# pc_healthypi_move_nRF5340_v1.net
KiCad netlist of a schematic drawn in EAGLE
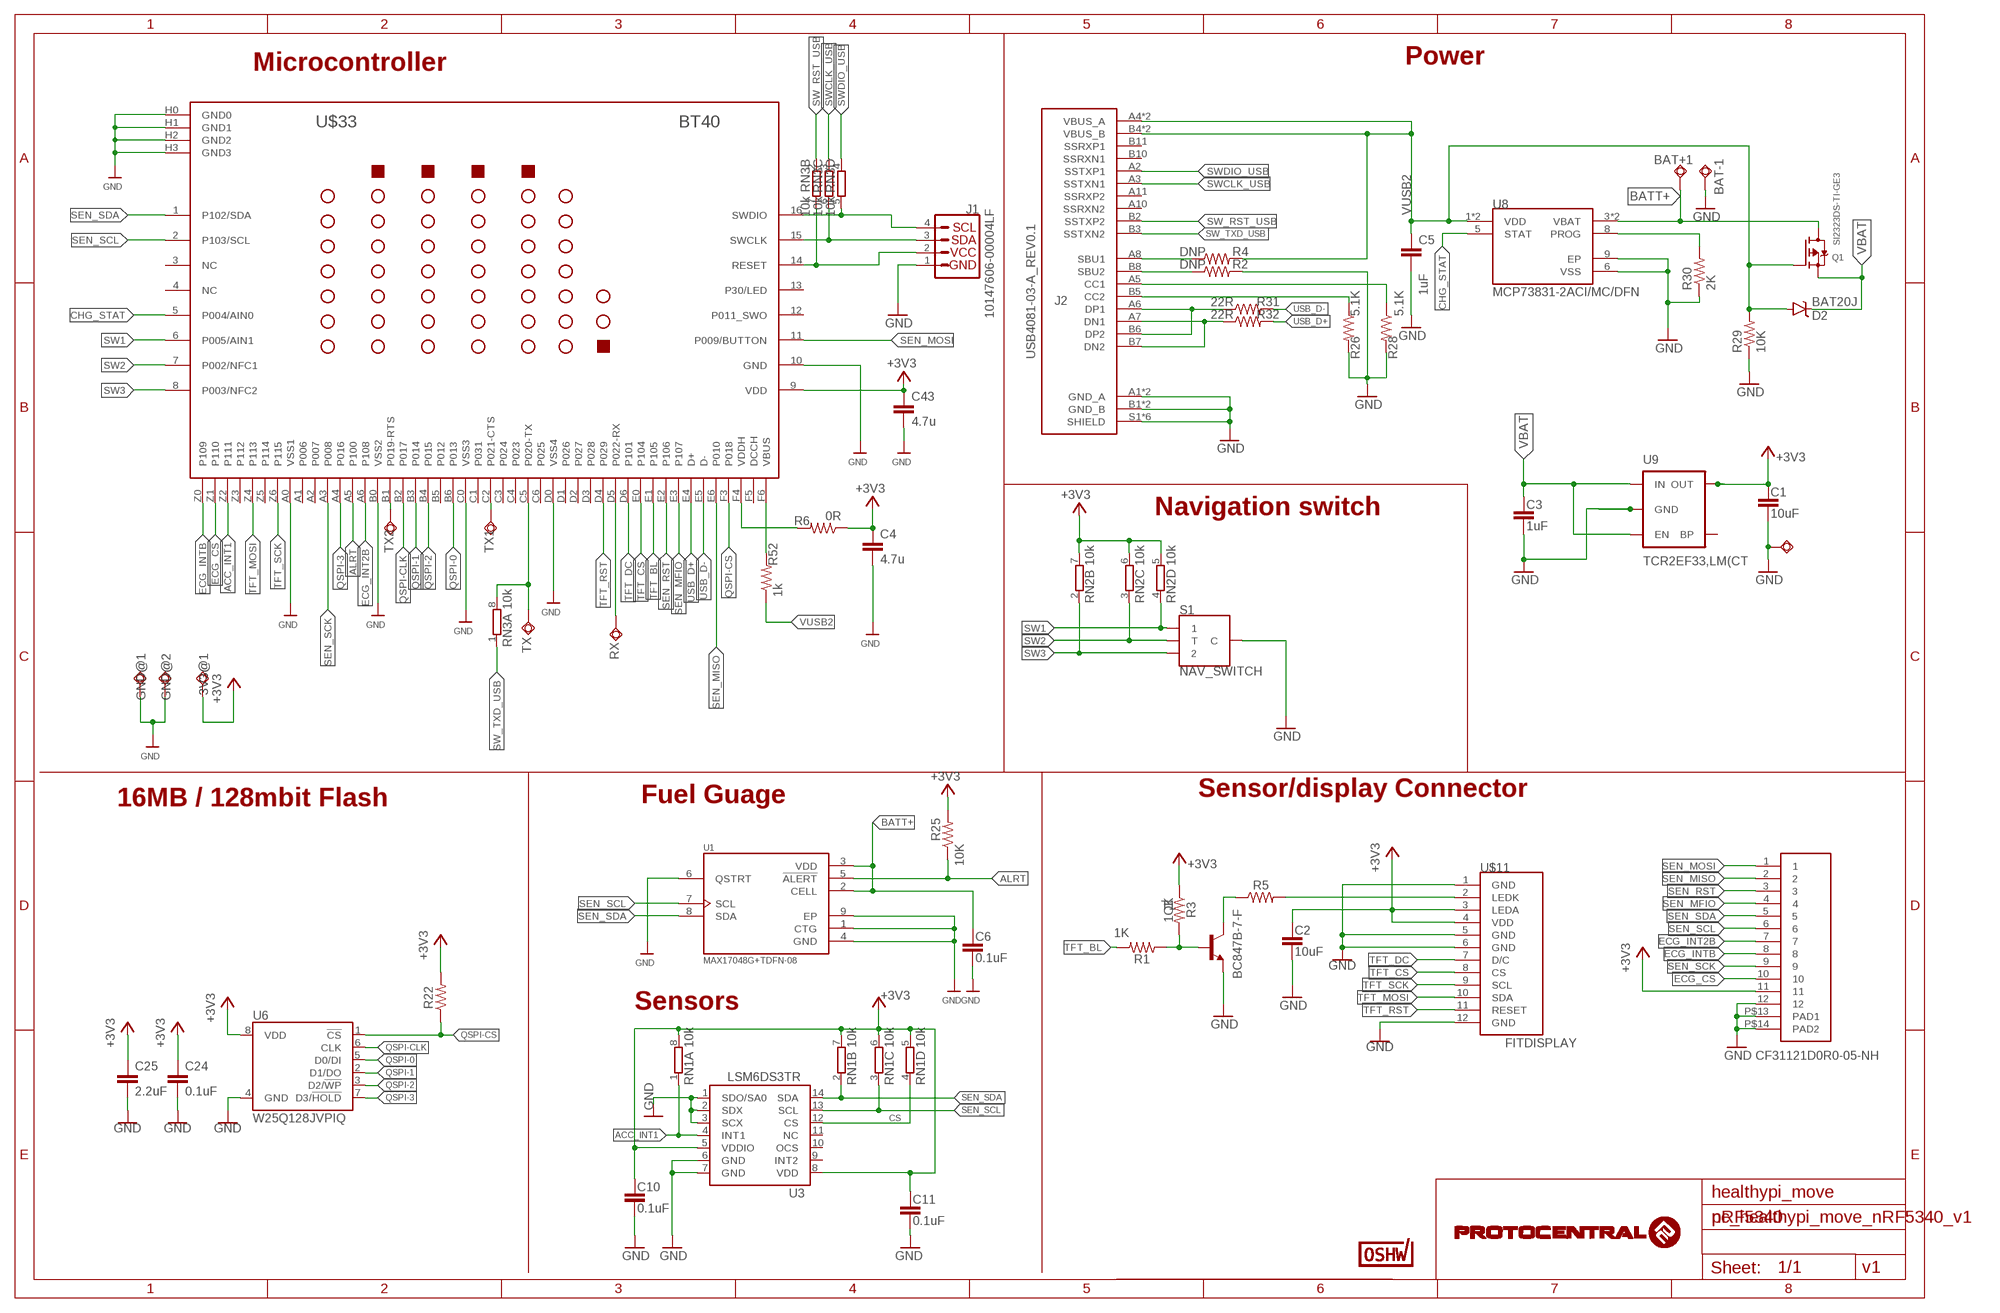
[diagram p0: schematic, sheet 1]

(export (version "E")
  (design (tool "Eeschema 10.0.6"))
  (components
    (comp (ref "3V3@1")
      (value "TPSQTP13SQ")
      (footprint "eagle-import:TP13SQ")
      (libsource (lib "eagle-import") (part "TPSQTP13SQ"))
    )
    (comp (ref "BAT+1")
      (value "TPSQTP13SQ")
      (footprint "eagle-import:TP13SQ")
      (libsource (lib "eagle-import") (part "TPSQTP13SQ"))
    )
    (comp (ref "BAT-1")
      (value "TPSQTP13SQ")
      (footprint "eagle-import:TP13SQ")
      (libsource (lib "eagle-import") (part "TPSQTP13SQ"))
    )
    (comp (ref "C1")
      (value "10uF")
      (footprint "eagle-import:0603@1")
      (libsource (lib "eagle-import") (part "0.1UF-0603-100V-10%"))
    )
    (comp (ref "C2")
      (value "10uF")
      (footprint "eagle-import:0603@1")
      (libsource (lib "eagle-import") (part "0.1UF-0603-100V-10%"))
    )
    (comp (ref "C3")
      (value "1uF")
      (footprint "eagle-import:0402-TIGHT")
      (libsource (lib "eagle-import") (part "0.1UF-0402T-6.3V-10%-X7R"))
    )
    (comp (ref "C4")
      (value "4.7u")
      (footprint "eagle-import:C0402")
      (libsource (lib "eagle-import") (part "C-EUC0402"))
    )
    (comp (ref "C5")
      (value "1uF")
      (footprint "eagle-import:0402-TIGHT")
      (libsource (lib "eagle-import") (part "2.2UF-0402_TIGHT-10V-10%-X5R"))
    )
    (comp (ref "C6")
      (value "0.1uF")
      (footprint "eagle-import:0402-TIGHT")
      (libsource (lib "eagle-import") (part "0.1UF-0402T-6.3V-10%-X7R"))
    )
    (comp (ref "C10")
      (value "0.1uF")
      (footprint "eagle-import:0402-TIGHT")
      (libsource (lib "eagle-import") (part "0.1UF-0402T-6.3V-10%-X7R"))
    )
    (comp (ref "C11")
      (value "0.1uF")
      (footprint "eagle-import:0402-TIGHT")
      (libsource (lib "eagle-import") (part "0.1UF-0402T-6.3V-10%-X7R"))
    )
    (comp (ref "C24")
      (value "0.1uF")
      (footprint "eagle-import:0402-TIGHT")
      (libsource (lib "eagle-import") (part "0.1UF-0402T-6.3V-10%-X7R"))
    )
    (comp (ref "C25")
      (value "2.2uF")
      (footprint "eagle-import:0402-TIGHT")
      (libsource (lib "eagle-import") (part "2.2UF-0402_TIGHT-10V-10%-X5R"))
    )
    (comp (ref "C43")
      (value "4.7u")
      (footprint "eagle-import:C0402")
      (libsource (lib "eagle-import") (part "C-EUC0402"))
    )
    (comp (ref "D2")
      (value "BAT20J")
      (footprint "eagle-import:SOD-323")
      (libsource (lib "eagle-import") (part "DIODE-SCHOTTKY-BAT20J"))
    )
    (comp (ref "GND@1")
      (value "TPSQTP13SQ")
      (footprint "eagle-import:TP13SQ")
      (libsource (lib "eagle-import") (part "TPSQTP13SQ"))
    )
    (comp (ref "GND@2")
      (value "TPSQTP13SQ")
      (footprint "eagle-import:TP13SQ")
      (libsource (lib "eagle-import") (part "TPSQTP13SQ"))
    )
    (comp (ref "J1")
      (value "10147606-00004LF")
      (footprint "eagle-import:JST04_1MM_RA")
      (libsource (lib "eagle-import") (part "QWIIC_CONNECTORJS-1MM"))
    )
    (comp (ref "J2")
      (value "USB4081-03-A_REV0.1")
      (footprint "eagle-import:GCT_USB4081-03-A_REV0.1")
      (fields (field (name "MF") "Global Connector Technology") (field (name "MP") "USB4081-03-A"))
      (libsource (lib "eagle-import") (part "USB4081-03-A_REV0.1"))
    )
    (comp (ref "Q1")
      (value "SI2323DS-TI-GE3")
      (footprint "eagle-import:SOT23-R")
      (libsource (lib "eagle-import") (part "MOSFET-P"))
    )
    (comp (ref "R1")
      (value "200")
      (footprint "eagle-import:R0402")
      (libsource (lib "eagle-import") (part "R-US_R0402"))
    )
    (comp (ref "R2")
      (value "DNP")
      (footprint "eagle-import:0402-RES")
      (libsource (lib "eagle-import") (part "RESISTOR0402-RES"))
    )
    (comp (ref "R3")
      (value "200")
      (footprint "eagle-import:R0402")
      (libsource (lib "eagle-import") (part "R-US_R0402"))
    )
    (comp (ref "R4")
      (value "DNP")
      (footprint "eagle-import:0402-RES")
      (libsource (lib "eagle-import") (part "RESISTOR0402-RES"))
    )
    (comp (ref "R5")
      (value "200R")
      (footprint "eagle-import:R0402")
      (libsource (lib "eagle-import") (part "R-US_R0402"))
    )
    (comp (ref "R6")
      (value "0R")
      (footprint "eagle-import:0402-RES")
      (libsource (lib "eagle-import") (part "RESISTOR0402-RES"))
    )
    (comp (ref "R22")
      (value "10k")
      (footprint "eagle-import:R0402")
      (libsource (lib "eagle-import") (part "R-US_R0402"))
    )
    (comp (ref "R25")
      (value "10K")
      (footprint "eagle-import:0402-RES")
      (libsource (lib "eagle-import") (part "RESISTOR0402-RES"))
    )
    (comp (ref "R26")
      (value "5.1K")
      (footprint "eagle-import:0402-RES")
      (libsource (lib "eagle-import") (part "RESISTOR0402-RES"))
    )
    (comp (ref "R28")
      (value "5.1K")
      (footprint "eagle-import:0402-RES")
      (libsource (lib "eagle-import") (part "RESISTOR0402-RES"))
    )
    (comp (ref "R29")
      (value "10K")
      (footprint "eagle-import:R0402")
      (libsource (lib "eagle-import") (part "R-US_R0402"))
    )
    (comp (ref "R30")
      (value "2K")
      (footprint "eagle-import:R0402")
      (libsource (lib "eagle-import") (part "R-US_R0402"))
    )
    (comp (ref "R31")
      (value "22R")
      (footprint "eagle-import:0402-RES")
      (libsource (lib "eagle-import") (part "RESISTOR0402-RES"))
    )
    (comp (ref "R32")
      (value "22R")
      (footprint "eagle-import:0402-RES")
      (libsource (lib "eagle-import") (part "RESISTOR0402-RES"))
    )
    (comp (ref "R52")
      (value "1k")
      (footprint "eagle-import:0402-RES")
      (libsource (lib "eagle-import") (part "RESISTOR0402-RES"))
    )
    (comp (ref "RN1")
      (value "10k")
      (footprint "eagle-import:4X0402ARV341")
      (libsource (lib "eagle-import") (part "4R-N0402ARV341"))
    )
    (comp (ref "RN2")
      (value "10k")
      (footprint "eagle-import:4X0402ARV341")
      (libsource (lib "eagle-import") (part "4R-N0402ARV341"))
    )
    (comp (ref "RN3")
      (value "10k")
      (footprint "eagle-import:4X0402ARV341")
      (libsource (lib "eagle-import") (part "4R-N0402ARV341"))
    )
    (comp (ref "RX")
      (value "TPSQTP13SQ")
      (footprint "eagle-import:TP13SQ")
      (libsource (lib "eagle-import") (part "TPSQTP13SQ"))
    )
    (comp (ref "S1")
      (value "NAV_SWITCH")
      (footprint "eagle-import:NAV_SWITCH")
      (libsource (lib "eagle-import") (part "NAV_SWITCH"))
    )
    (comp (ref "SWIO6")
      (value "TPSQTP11R")
      (footprint "eagle-import:TP11R")
      (libsource (lib "eagle-import") (part "TPSQTP11R"))
    )
    (comp (ref "T1")
      (value "BC847B-7-F")
      (footprint "eagle-import:SOT23-BEC")
      (libsource (lib "eagle-import") (part "-NPN-SOT23-BECMMBT2222ALT1"))
    )
    (comp (ref "TX")
      (value "TPSQTP13SQ")
      (footprint "eagle-import:TP13SQ")
      (libsource (lib "eagle-import") (part "TPSQTP13SQ"))
    )
    (comp (ref "TX1")
      (value "TPSQTP13SQ")
      (footprint "eagle-import:TP13SQ")
      (libsource (lib "eagle-import") (part "TPSQTP13SQ"))
    )
    (comp (ref "TX2")
      (value "TPSQTP13SQ")
      (footprint "eagle-import:TP13SQ")
      (libsource (lib "eagle-import") (part "TPSQTP13SQ"))
    )
    (comp (ref "U$5")
      (value "CF31121D0R0-05-NH")
      (footprint "eagle-import:CF31121D0R0-05-NH")
      (libsource (lib "eagle-import") (part "CF31121D0R0-05-NH"))
    )
    (comp (ref "U$9")
      (value "CERT-SMALL")
      (footprint "eagle-import:CERT-SMALL-SILK")
      (libsource (lib "eagle-import") (part "CERT-SMALL"))
    )
    (comp (ref "U$11")
      (value "FITDISPLAY")
      (footprint "eagle-import:FITDISPLAY")
      (libsource (lib "eagle-import") (part "FITDISPLAY"))
    )
    (comp (ref "U$33")
      (value "BT40")
      (footprint "eagle-import:BT40")
      (libsource (lib "eagle-import") (part "BT40"))
    )
    (comp (ref "U1")
      (value "MAX17048G+TDFN-08")
      (footprint "eagle-import:SON50P200X200X80-9N")
      (fields (field (name "MF") "Analog Devices") (field (name "MP") "MAX17048G+"))
      (libsource (lib "eagle-import") (part "MAX17048G+TDFN-08"))
    )
    (comp (ref "U3")
      (value "LSM6DS3TR")
      (footprint "eagle-import:LGA14L")
      (libsource (lib "eagle-import") (part "LSM6DS3"))
    )
    (comp (ref "U6")
      (value "W25Q128JVPIQ")
      (footprint "eagle-import:WSON-8-6X5-SKINNY_CENTERPAD")
      (libsource (lib "eagle-import") (part "W25QXX128MBIT-6X5-SKINNY_CENTER"))
    )
    (comp (ref "U8")
      (value "MCP73831-2ACI/MC/DFN")
      (footprint "eagle-import:SON50P200X300X100-9N")
      (fields (field (name "MF") "Microchip Technology") (field (name "MP") "MCP73831-2ACI/MC"))
      (libsource (lib "eagle-import") (part "MCP73831-2ACI/MC/DFN"))
    )
    (comp (ref "U9")
      (value "TCR2EF33,LM(CT")
      (footprint "eagle-import:SOT23-5")
      (libsource (lib "eagle-import") (part "V_REG_LDOSMD"))
    )
  )
  (nets
    (net (code "1") (name "+3V3") (class "Default")
      (node (ref "3V3@1") (pin "TP") (pinfunction "TP_TP") (pintype "input"))
      (node (ref "C1") (pin "1") (pinfunction "1_1") (pintype "passive"))
      (node (ref "C10") (pin "1") (pinfunction "1_1") (pintype "passive"))
      (node (ref "C11") (pin "1") (pinfunction "1_1") (pintype "passive"))
      (node (ref "C2") (pin "1") (pinfunction "1_1") (pintype "passive"))
      (node (ref "C24") (pin "1") (pinfunction "1_1") (pintype "passive"))
      (node (ref "C25") (pin "1") (pinfunction "1_1") (pintype "passive"))
      (node (ref "C4") (pin "1") (pinfunction "1_1") (pintype "passive"))
      (node (ref "C43") (pin "1") (pinfunction "1_1") (pintype "passive"))
      (node (ref "R22") (pin "2") (pinfunction "2_2") (pintype "passive"))
      (node (ref "R25") (pin "2") (pinfunction "2_2") (pintype "passive"))
      (node (ref "R3") (pin "1") (pinfunction "1_1") (pintype "passive"))
      (node (ref "R6") (pin "1") (pinfunction "1_1") (pintype "passive"))
      (node (ref "RN1") (pin "5") (pinfunction "2_5") (pintype "passive"))
      (node (ref "RN1") (pin "6") (pinfunction "2_6") (pintype "passive"))
      (node (ref "RN1") (pin "7") (pinfunction "2_7") (pintype "passive"))
      (node (ref "RN1") (pin "8") (pinfunction "2_8") (pintype "passive"))
      (node (ref "RN2") (pin "5") (pinfunction "2_5") (pintype "passive"))
      (node (ref "RN2") (pin "6") (pinfunction "2_6") (pintype "passive"))
      (node (ref "RN2") (pin "7") (pinfunction "2_7") (pintype "passive"))
      (node (ref "U$11") (pin "3") (pinfunction "LEDA_3") (pintype "bidirectional"))
      (node (ref "U$11") (pin "4") (pinfunction "VDD_4") (pintype "bidirectional"))
      (node (ref "U$33") (pin "9") (pinfunction "VDD_9") (pintype "bidirectional"))
      (node (ref "U$5") (pin "11") (pinfunction "11_11") (pintype "bidirectional"))
      (node (ref "U3") (pin "5") (pinfunction "VDDIO_5") (pintype "bidirectional"))
      (node (ref "U3") (pin "8") (pinfunction "VDD_8") (pintype "bidirectional"))
      (node (ref "U6") (pin "8") (pinfunction "VDD_8") (pintype "bidirectional"))
      (node (ref "U9") (pin "5") (pinfunction "OUT_5") (pintype "passive"))
    )
    (net (code "2") (name "/CS") (class "Default")
      (node (ref "RN1") (pin "4") (pinfunction "1_4") (pintype "passive"))
      (node (ref "U3") (pin "12") (pinfunction "CS_12") (pintype "bidirectional"))
    )
    (net (code "3") (name "ACC_INT1") (class "Default")
      (node (ref "RN1") (pin "1") (pinfunction "1_1") (pintype "passive"))
      (node (ref "U$33") (pin "Z2") (pinfunction "P111_Z2") (pintype "bidirectional"))
      (node (ref "U3") (pin "4") (pinfunction "INT1_4") (pintype "bidirectional"))
    )
    (net (code "4") (name "ALRT") (class "Default")
      (node (ref "R25") (pin "1") (pinfunction "1_1") (pintype "passive"))
      (node (ref "U$33") (pin "A5") (pinfunction "P100_A5") (pintype "bidirectional"))
      (node (ref "U1") (pin "5") (pinfunction "~{ALERT}_5") (pintype "output"))
    )
    (net (code "5") (name "BATT+") (class "Default")
      (node (ref "BAT+1") (pin "TP") (pinfunction "TP_TP") (pintype "input"))
      (node (ref "C6") (pin "1") (pinfunction "1_1") (pintype "passive"))
      (node (ref "Q1") (pin "3") (pinfunction "D_3") (pintype "passive"))
      (node (ref "U1") (pin "2") (pinfunction "CELL_2") (pintype "power_in"))
      (node (ref "U1") (pin "3") (pinfunction "VDD_3") (pintype "power_in"))
      (node (ref "U8") (pin "3") (pinfunction "VBAT_3") (pintype "output"))
      (node (ref "U8") (pin "4") (pinfunction "VBAT_4") (pintype "output"))
    )
    (net (code "6") (name "CHG_STAT") (class "Default")
      (node (ref "U$33") (pin "5") (pinfunction "P004/AIN0_5") (pintype "bidirectional"))
      (node (ref "U8") (pin "5") (pinfunction "STAT_5") (pintype "output"))
    )
    (net (code "7") (name "ECG_CS") (class "Default")
      (node (ref "U$33") (pin "Z1") (pinfunction "P110_Z1") (pintype "bidirectional"))
      (node (ref "U$5") (pin "10") (pinfunction "10_10") (pintype "bidirectional"))
    )
    (net (code "8") (name "ECG_INT2B") (class "Default")
      (node (ref "U$33") (pin "A6") (pinfunction "P108_A6") (pintype "bidirectional"))
      (node (ref "U$5") (pin "7") (pinfunction "7_7") (pintype "bidirectional"))
    )
    (net (code "9") (name "ECG_INTB") (class "Default")
      (node (ref "U$33") (pin "Z0") (pinfunction "P109_Z0") (pintype "bidirectional"))
      (node (ref "U$5") (pin "8") (pinfunction "8_8") (pintype "bidirectional"))
    )
    (net (code "10") (name "GND") (class "Default")
      (node (ref "BAT-1") (pin "TP") (pinfunction "TP_TP") (pintype "input"))
      (node (ref "C1") (pin "2") (pinfunction "2_2") (pintype "passive"))
      (node (ref "C10") (pin "2") (pinfunction "2_2") (pintype "passive"))
      (node (ref "C11") (pin "2") (pinfunction "2_2") (pintype "passive"))
      (node (ref "C2") (pin "2") (pinfunction "2_2") (pintype "passive"))
      (node (ref "C24") (pin "2") (pinfunction "2_2") (pintype "passive"))
      (node (ref "C25") (pin "2") (pinfunction "2_2") (pintype "passive"))
      (node (ref "C3") (pin "2") (pinfunction "2_2") (pintype "passive"))
      (node (ref "C4") (pin "2") (pinfunction "2_2") (pintype "passive"))
      (node (ref "C43") (pin "2") (pinfunction "2_2") (pintype "passive"))
      (node (ref "C5") (pin "2") (pinfunction "2_2") (pintype "passive"))
      (node (ref "C6") (pin "2") (pinfunction "2_2") (pintype "passive"))
      (node (ref "GND@1") (pin "TP") (pinfunction "TP_TP") (pintype "input"))
      (node (ref "GND@2") (pin "TP") (pinfunction "TP_TP") (pintype "input"))
      (node (ref "J1") (pin "1") (pinfunction "1_1") (pintype "power_in"))
      (node (ref "J2") (pin "A1") (pinfunction "GND_A_A1") (pintype "power_in"))
      (node (ref "J2") (pin "A12") (pinfunction "GND_A_A12") (pintype "power_in"))
      (node (ref "J2") (pin "B1") (pinfunction "GND_B_B1") (pintype "power_in"))
      (node (ref "J2") (pin "B12") (pinfunction "GND_B_B12") (pintype "power_in"))
      (node (ref "J2") (pin "S1") (pinfunction "SHIELD_S1") (pintype "passive"))
      (node (ref "J2") (pin "S2") (pinfunction "SHIELD_S2") (pintype "passive"))
      (node (ref "J2") (pin "S3") (pinfunction "SHIELD_S3") (pintype "passive"))
      (node (ref "J2") (pin "S4") (pinfunction "SHIELD_S4") (pintype "passive"))
      (node (ref "J2") (pin "S5") (pinfunction "SHIELD_S5") (pintype "passive"))
      (node (ref "J2") (pin "S6") (pinfunction "SHIELD_S6") (pintype "passive"))
      (node (ref "R2") (pin "2") (pinfunction "2_2") (pintype "passive"))
      (node (ref "R26") (pin "2") (pinfunction "2_2") (pintype "passive"))
      (node (ref "R28") (pin "2") (pinfunction "2_2") (pintype "passive"))
      (node (ref "R29") (pin "1") (pinfunction "1_1") (pintype "passive"))
      (node (ref "R30") (pin "1") (pinfunction "1_1") (pintype "passive"))
      (node (ref "S1") (pin "C") (pinfunction "C_C") (pintype "power_in"))
      (node (ref "SWIO6") (pin "TP") (pinfunction "TP_TP") (pintype "input"))
      (node (ref "T1") (pin "E") (pinfunction "E_E") (pintype "passive"))
      (node (ref "U$11") (pin "1") (pinfunction "GND_1") (pintype "bidirectional"))
      (node (ref "U$11") (pin "12") (pinfunction "GND_12") (pintype "bidirectional"))
      (node (ref "U$11") (pin "5") (pinfunction "GND_5") (pintype "bidirectional"))
      (node (ref "U$11") (pin "6") (pinfunction "GND_6") (pintype "bidirectional"))
      (node (ref "U$33") (pin "10") (pinfunction "GND_10") (pintype "bidirectional"))
      (node (ref "U$33") (pin "A0") (pinfunction "VSS1_A0") (pintype "bidirectional"))
      (node (ref "U$33") (pin "B0") (pinfunction "VSS2_B0") (pintype "bidirectional"))
      (node (ref "U$33") (pin "C0") (pinfunction "VSS3_C0") (pintype "bidirectional"))
      (node (ref "U$33") (pin "D0") (pinfunction "VSS4_D0") (pintype "bidirectional"))
      (node (ref "U$33") (pin "H0") (pinfunction "GND0_H0") (pintype "bidirectional"))
      (node (ref "U$33") (pin "H1") (pinfunction "GND1_H1") (pintype "bidirectional"))
      (node (ref "U$33") (pin "H2") (pinfunction "GND2_H2") (pintype "bidirectional"))
      (node (ref "U$33") (pin "H3") (pinfunction "GND3_H3") (pintype "bidirectional"))
      (node (ref "U$5") (pin "12") (pinfunction "12_12") (pintype "bidirectional"))
      (node (ref "U$5") (pin "P$13") (pinfunction "PAD1_P$13") (pintype "bidirectional"))
      (node (ref "U$5") (pin "P$14") (pinfunction "PAD2_P$14") (pintype "bidirectional"))
      (node (ref "U1") (pin "1") (pinfunction "CTG_1") (pintype "power_in"))
      (node (ref "U1") (pin "4") (pinfunction "GND_4") (pintype "power_in"))
      (node (ref "U1") (pin "6") (pinfunction "QSTRT_6") (pintype "input"))
      (node (ref "U1") (pin "9") (pinfunction "EP_9") (pintype "power_in"))
      (node (ref "U3") (pin "1") (pinfunction "SDO/SA0_1") (pintype "bidirectional"))
      (node (ref "U3") (pin "2") (pinfunction "SDX_2") (pintype "bidirectional"))
      (node (ref "U3") (pin "3") (pinfunction "SCX_3") (pintype "bidirectional"))
      (node (ref "U3") (pin "6") (pinfunction "GND_6") (pintype "bidirectional"))
      (node (ref "U3") (pin "7") (pinfunction "GND_7") (pintype "bidirectional"))
      (node (ref "U6") (pin "4") (pinfunction "GND_4") (pintype "bidirectional"))
      (node (ref "U8") (pin "6") (pinfunction "VSS_6") (pintype "power_in"))
      (node (ref "U8") (pin "9") (pinfunction "EP_9") (pintype "power_in"))
      (node (ref "U9") (pin "2") (pinfunction "GND_2") (pintype "input"))
    )
    (net (code "11") (name "Net-(J2-CC1)") (class "Default")
      (node (ref "J2") (pin "A5") (pinfunction "CC1_A5") (pintype "bidirectional"))
      (node (ref "R28") (pin "1") (pinfunction "1_1") (pintype "passive"))
    )
    (net (code "12") (name "Net-(J2-CC2)") (class "Default")
      (node (ref "J2") (pin "B5") (pinfunction "CC2_B5") (pintype "bidirectional"))
      (node (ref "R26") (pin "1") (pinfunction "1_1") (pintype "passive"))
    )
    (net (code "13") (name "Net-(J2-DN1)") (class "Default")
      (node (ref "J2") (pin "A7") (pinfunction "DN1_A7") (pintype "bidirectional"))
      (node (ref "J2") (pin "B7") (pinfunction "DN2_B7") (pintype "bidirectional"))
      (node (ref "R32") (pin "1") (pinfunction "1_1") (pintype "passive"))
    )
    (net (code "14") (name "Net-(J2-DP1)") (class "Default")
      (node (ref "J2") (pin "A6") (pinfunction "DP1_A6") (pintype "bidirectional"))
      (node (ref "J2") (pin "B6") (pinfunction "DP2_B6") (pintype "bidirectional"))
      (node (ref "R31") (pin "1") (pinfunction "1_1") (pintype "passive"))
    )
    (net (code "15") (name "Net-(J2-SBU1)") (class "Default")
      (node (ref "J2") (pin "A8") (pinfunction "SBU1_A8") (pintype "bidirectional"))
      (node (ref "R4") (pin "1") (pinfunction "1_1") (pintype "passive"))
    )
    (net (code "16") (name "Net-(J2-SBU2)") (class "Default")
      (node (ref "J2") (pin "B8") (pinfunction "SBU2_B8") (pintype "bidirectional"))
      (node (ref "R2") (pin "1") (pinfunction "1_1") (pintype "passive"))
    )
    (net (code "17") (name "Net-(R1-Pad1)") (class "Default")
      (node (ref "R1") (pin "1") (pinfunction "1_1") (pintype "passive"))
      (node (ref "R3") (pin "2") (pinfunction "2_2") (pintype "passive"))
      (node (ref "T1") (pin "B") (pinfunction "B_B") (pintype "passive"))
    )
    (net (code "18") (name "Net-(R5-Pad1)") (class "Default")
      (node (ref "R5") (pin "1") (pinfunction "1_1") (pintype "passive"))
      (node (ref "T1") (pin "C") (pinfunction "C_C") (pintype "passive"))
    )
    (net (code "19") (name "Net-(RN3A-2)") (class "Default")
      (node (ref "RN3") (pin "8") (pinfunction "2_8") (pintype "passive"))
      (node (ref "TX") (pin "TP") (pinfunction "TP_TP") (pintype "input"))
      (node (ref "U$33") (pin "C5") (pinfunction "P020-TX_C5") (pintype "bidirectional"))
    )
    (net (code "20") (name "Net-(RN3B-2)") (class "Default")
      (node (ref "J1") (pin "2") (pinfunction "2_2") (pintype "power_in"))
      (node (ref "RN3") (pin "7") (pinfunction "2_7") (pintype "passive"))
      (node (ref "U$33") (pin "14") (pinfunction "RESET_14") (pintype "bidirectional"))
    )
    (net (code "21") (name "Net-(RN3C-2)") (class "Default")
      (node (ref "J1") (pin "3") (pinfunction "3_3") (pintype "passive"))
      (node (ref "RN3") (pin "6") (pinfunction "2_6") (pintype "passive"))
      (node (ref "U$33") (pin "15") (pinfunction "SWCLK_15") (pintype "bidirectional"))
    )
    (net (code "22") (name "Net-(RN3D-2)") (class "Default")
      (node (ref "J1") (pin "4") (pinfunction "4_4") (pintype "passive"))
      (node (ref "RN3") (pin "5") (pinfunction "2_5") (pintype "passive"))
      (node (ref "U$33") (pin "16") (pinfunction "SWDIO_16") (pintype "bidirectional"))
    )
    (net (code "23") (name "Net-(U$11-LEDK)") (class "Default")
      (node (ref "R5") (pin "2") (pinfunction "2_2") (pintype "passive"))
      (node (ref "U$11") (pin "2") (pinfunction "LEDK_2") (pintype "bidirectional"))
    )
    (net (code "24") (name "Net-(U$33-P019-RTS)") (class "Default")
      (node (ref "TX2") (pin "TP") (pinfunction "TP_TP") (pintype "input"))
      (node (ref "U$33") (pin "B1") (pinfunction "P019-RTS_B1") (pintype "bidirectional"))
    )
    (net (code "25") (name "Net-(U$33-P021-CTS)") (class "Default")
      (node (ref "TX1") (pin "TP") (pinfunction "TP_TP") (pintype "input"))
      (node (ref "U$33") (pin "C2") (pinfunction "P021-CTS_C2") (pintype "bidirectional"))
    )
    (net (code "26") (name "Net-(U$33-P022-RX)") (class "Default")
      (node (ref "RX") (pin "TP") (pinfunction "TP_TP") (pintype "input"))
      (node (ref "U$33") (pin "D5") (pinfunction "P022-RX_D5") (pintype "bidirectional"))
    )
    (net (code "27") (name "Net-(U$33-VBUS)") (class "Default")
      (node (ref "R52") (pin "2") (pinfunction "2_2") (pintype "passive"))
      (node (ref "U$33") (pin "F6") (pinfunction "VBUS_F6") (pintype "bidirectional"))
    )
    (net (code "28") (name "Net-(U$33-VDDH)") (class "Default")
      (node (ref "R6") (pin "2") (pinfunction "2_2") (pintype "passive"))
      (node (ref "U$33") (pin "F4") (pinfunction "VDDH_F4") (pintype "bidirectional"))
    )
    (net (code "29") (name "Net-(U8-PROG)") (class "Default")
      (node (ref "R30") (pin "2") (pinfunction "2_2") (pintype "passive"))
      (node (ref "U8") (pin "8") (pinfunction "PROG_8") (pintype "input"))
    )
    (net (code "30") (name "QSPI-0") (class "Default")
      (node (ref "U$33") (pin "B6") (pinfunction "P013_B6") (pintype "bidirectional"))
      (node (ref "U6") (pin "5") (pinfunction "D0/DI_5") (pintype "bidirectional"))
    )
    (net (code "31") (name "QSPI-1") (class "Default")
      (node (ref "U$33") (pin "B3") (pinfunction "P014_B3") (pintype "bidirectional"))
      (node (ref "U6") (pin "2") (pinfunction "D1/DO_2") (pintype "bidirectional"))
    )
    (net (code "32") (name "QSPI-2") (class "Default")
      (node (ref "U$33") (pin "B4") (pinfunction "P015_B4") (pintype "bidirectional"))
      (node (ref "U6") (pin "3") (pinfunction "D2/~{WP}_3") (pintype "bidirectional"))
    )
    (net (code "33") (name "QSPI-3") (class "Default")
      (node (ref "U$33") (pin "A4") (pinfunction "P016_A4") (pintype "bidirectional"))
      (node (ref "U6") (pin "7") (pinfunction "D3/~{HOLD}_7") (pintype "bidirectional"))
    )
    (net (code "34") (name "QSPI-CLK") (class "Default")
      (node (ref "U$33") (pin "B2") (pinfunction "P017_B2") (pintype "bidirectional"))
      (node (ref "U6") (pin "6") (pinfunction "CLK_6") (pintype "bidirectional"))
    )
    (net (code "35") (name "QSPI-CS") (class "Default")
      (node (ref "R22") (pin "1") (pinfunction "1_1") (pintype "passive"))
      (node (ref "U$33") (pin "F3") (pinfunction "P018_F3") (pintype "bidirectional"))
      (node (ref "U6") (pin "1") (pinfunction "~{CS}_1") (pintype "bidirectional"))
    )
    (net (code "36") (name "SEN_MFIO") (class "Default")
      (node (ref "U$33") (pin "E3") (pinfunction "P107_E3") (pintype "bidirectional"))
      (node (ref "U$5") (pin "4") (pinfunction "4_4") (pintype "bidirectional"))
    )
    (net (code "37") (name "SEN_MISO") (class "Default")
      (node (ref "U$33") (pin "E6") (pinfunction "P010_E6") (pintype "bidirectional"))
      (node (ref "U$5") (pin "2") (pinfunction "2_2") (pintype "bidirectional"))
    )
    (net (code "38") (name "SEN_MOSI") (class "Default")
      (node (ref "U$33") (pin "11") (pinfunction "P009/BUTTON_11") (pintype "bidirectional"))
      (node (ref "U$5") (pin "1") (pinfunction "1_1") (pintype "bidirectional"))
    )
    (net (code "39") (name "SEN_RST") (class "Default")
      (node (ref "U$33") (pin "E2") (pinfunction "P106_E2") (pintype "bidirectional"))
      (node (ref "U$5") (pin "3") (pinfunction "3_3") (pintype "bidirectional"))
    )
    (net (code "40") (name "SEN_SCK") (class "Default")
      (node (ref "U$33") (pin "A3") (pinfunction "P008_A3") (pintype "bidirectional"))
      (node (ref "U$5") (pin "9") (pinfunction "9_9") (pintype "bidirectional"))
    )
    (net (code "41") (name "SEN_SCL") (class "Default")
      (node (ref "RN1") (pin "3") (pinfunction "1_3") (pintype "passive"))
      (node (ref "U$33") (pin "2") (pinfunction "P103/SCL_2") (pintype "bidirectional"))
      (node (ref "U$5") (pin "6") (pinfunction "6_6") (pintype "bidirectional"))
      (node (ref "U1") (pin "7") (pinfunction "SCL_7") (pintype "input"))
      (node (ref "U3") (pin "13") (pinfunction "SCL_13") (pintype "bidirectional"))
    )
    (net (code "42") (name "SEN_SDA") (class "Default")
      (node (ref "RN1") (pin "2") (pinfunction "1_2") (pintype "passive"))
      (node (ref "U$33") (pin "1") (pinfunction "P102/SDA_1") (pintype "bidirectional"))
      (node (ref "U$5") (pin "5") (pinfunction "5_5") (pintype "bidirectional"))
      (node (ref "U1") (pin "8") (pinfunction "SDA_8") (pintype "bidirectional"))
      (node (ref "U3") (pin "14") (pinfunction "SDA_14") (pintype "bidirectional"))
    )
    (net (code "43") (name "SW1") (class "Default")
      (node (ref "RN2") (pin "4") (pinfunction "1_4") (pintype "passive"))
      (node (ref "S1") (pin "1") (pinfunction "1_1") (pintype "input"))
      (node (ref "U$33") (pin "6") (pinfunction "P005/AIN1_6") (pintype "bidirectional"))
    )
    (net (code "44") (name "SW2") (class "Default")
      (node (ref "RN2") (pin "3") (pinfunction "1_3") (pintype "passive"))
      (node (ref "S1") (pin "T") (pinfunction "T_T") (pintype "input"))
      (node (ref "U$33") (pin "7") (pinfunction "P002/NFC1_7") (pintype "bidirectional"))
    )
    (net (code "45") (name "SW3") (class "Default")
      (node (ref "RN2") (pin "2") (pinfunction "1_2") (pintype "passive"))
      (node (ref "S1") (pin "2") (pinfunction "2_2") (pintype "input"))
      (node (ref "U$33") (pin "8") (pinfunction "P003/NFC2_8") (pintype "bidirectional"))
    )
    (net (code "46") (name "SWCLK_USB") (class "Default")
      (node (ref "J2") (pin "A3") (pinfunction "SSTXN1_A3") (pintype "bidirectional"))
      (node (ref "RN3") (pin "3") (pinfunction "1_3") (pintype "passive"))
    )
    (net (code "47") (name "SWDIO_USB") (class "Default")
      (node (ref "J2") (pin "A2") (pinfunction "SSTXP1_A2") (pintype "bidirectional"))
      (node (ref "RN3") (pin "4") (pinfunction "1_4") (pintype "passive"))
    )
    (net (code "48") (name "SW_RST_USB") (class "Default")
      (node (ref "J2") (pin "B2") (pinfunction "SSTXP2_B2") (pintype "bidirectional"))
      (node (ref "RN3") (pin "2") (pinfunction "1_2") (pintype "passive"))
    )
    (net (code "49") (name "SW_TXD_USB") (class "Default")
      (node (ref "J2") (pin "B3") (pinfunction "SSTXN2_B3") (pintype "bidirectional"))
      (node (ref "RN3") (pin "1") (pinfunction "1_1") (pintype "passive"))
    )
    (net (code "50") (name "TFT_BL") (class "Default")
      (node (ref "R1") (pin "2") (pinfunction "2_2") (pintype "passive"))
      (node (ref "U$33") (pin "E1") (pinfunction "P105_E1") (pintype "bidirectional"))
    )
    (net (code "51") (name "TFT_CS") (class "Default")
      (node (ref "U$11") (pin "8") (pinfunction "CS_8") (pintype "bidirectional"))
      (node (ref "U$33") (pin "E0") (pinfunction "P104_E0") (pintype "bidirectional"))
    )
    (net (code "52") (name "TFT_DC") (class "Default")
      (node (ref "U$11") (pin "7") (pinfunction "D/C_7") (pintype "bidirectional"))
      (node (ref "U$33") (pin "D6") (pinfunction "P101_D6") (pintype "bidirectional"))
    )
    (net (code "53") (name "TFT_MOSI") (class "Default")
      (node (ref "U$11") (pin "10") (pinfunction "SDA_10") (pintype "bidirectional"))
      (node (ref "U$33") (pin "Z4") (pinfunction "P113_Z4") (pintype "bidirectional"))
    )
    (net (code "54") (name "TFT_RST") (class "Default")
      (node (ref "U$11") (pin "11") (pinfunction "RESET_11") (pintype "bidirectional"))
      (node (ref "U$33") (pin "D4") (pinfunction "P029_D4") (pintype "bidirectional"))
    )
    (net (code "55") (name "TFT_SCK") (class "Default")
      (node (ref "U$11") (pin "9") (pinfunction "SCL_9") (pintype "bidirectional"))
      (node (ref "U$33") (pin "Z6") (pinfunction "P115_Z6") (pintype "bidirectional"))
    )
    (net (code "56") (name "USB_D+") (class "Default")
      (node (ref "R32") (pin "2") (pinfunction "2_2") (pintype "passive"))
      (node (ref "U$33") (pin "E4") (pinfunction "D+_E4") (pintype "bidirectional"))
    )
    (net (code "57") (name "USB_D-") (class "Default")
      (node (ref "R31") (pin "2") (pinfunction "2_2") (pintype "passive"))
      (node (ref "U$33") (pin "E5") (pinfunction "D-_E5") (pintype "bidirectional"))
    )
    (net (code "58") (name "VBAT") (class "Default")
      (node (ref "C3") (pin "1") (pinfunction "1_1") (pintype "passive"))
      (node (ref "D2") (pin "C") (pinfunction "C_C") (pintype "passive"))
      (node (ref "Q1") (pin "2") (pinfunction "S_2") (pintype "passive"))
      (node (ref "U9") (pin "1") (pinfunction "IN_1") (pintype "input"))
      (node (ref "U9") (pin "3") (pinfunction "EN_3") (pintype "input"))
    )
    (net (code "59") (name "VUSB2") (class "Default")
      (node (ref "C5") (pin "1") (pinfunction "1_1") (pintype "passive"))
      (node (ref "D2") (pin "A") (pinfunction "A_A") (pintype "passive"))
      (node (ref "J2") (pin "A4") (pinfunction "VBUS_A_A4") (pintype "power_in"))
      (node (ref "J2") (pin "A9") (pinfunction "VBUS_A_A9") (pintype "power_in"))
      (node (ref "J2") (pin "B4") (pinfunction "VBUS_B_B4") (pintype "power_in"))
      (node (ref "J2") (pin "B9") (pinfunction "VBUS_B_B9") (pintype "power_in"))
      (node (ref "Q1") (pin "1") (pinfunction "G_1") (pintype "passive"))
      (node (ref "R29") (pin "2") (pinfunction "2_2") (pintype "passive"))
      (node (ref "R4") (pin "2") (pinfunction "2_2") (pintype "passive"))
      (node (ref "R52") (pin "1") (pinfunction "1_1") (pintype "passive"))
      (node (ref "U8") (pin "1") (pinfunction "VDD_1") (pintype "power_in"))
      (node (ref "U8") (pin "2") (pinfunction "VDD_2") (pintype "power_in"))
    )
    (net (code "60") (name "unconnected-(J2-SSRXN1-PadB10)") (class "Default")
      (node (ref "J2") (pin "B10") (pinfunction "SSRXN1_B10") (pintype "bidirectional"))
    )
    (net (code "61") (name "unconnected-(J2-SSRXN2-PadA10)") (class "Default")
      (node (ref "J2") (pin "A10") (pinfunction "SSRXN2_A10") (pintype "bidirectional"))
    )
    (net (code "62") (name "unconnected-(J2-SSRXP1-PadB11)") (class "Default")
      (node (ref "J2") (pin "B11") (pinfunction "SSRXP1_B11") (pintype "bidirectional"))
    )
    (net (code "63") (name "unconnected-(J2-SSRXP2-PadA11)") (class "Default")
      (node (ref "J2") (pin "A11") (pinfunction "SSRXP2_A11") (pintype "bidirectional"))
    )
    (net (code "64") (name "unconnected-(U$33-DCCH-PadF5)") (class "Default")
      (node (ref "U$33") (pin "F5") (pinfunction "DCCH_F5") (pintype "bidirectional"))
    )
    (net (code "65") (name "unconnected-(U$33-NC-Pad3)") (class "Default")
      (node (ref "U$33") (pin "3") (pinfunction "NC_3") (pintype "bidirectional"))
    )
    (net (code "66") (name "unconnected-(U$33-NC-Pad4)") (class "Default")
      (node (ref "U$33") (pin "4") (pinfunction "NC_4") (pintype "bidirectional"))
    )
    (net (code "67") (name "unconnected-(U$33-P006-PadA1)") (class "Default")
      (node (ref "U$33") (pin "A1") (pinfunction "P006_A1") (pintype "bidirectional"))
    )
    (net (code "68") (name "unconnected-(U$33-P007-PadA2)") (class "Default")
      (node (ref "U$33") (pin "A2") (pinfunction "P007_A2") (pintype "bidirectional"))
    )
    (net (code "69") (name "unconnected-(U$33-P011_SWO-Pad12)") (class "Default")
      (node (ref "U$33") (pin "12") (pinfunction "P011_SWO_12") (pintype "bidirectional"))
    )
    (net (code "70") (name "unconnected-(U$33-P012-PadB5)") (class "Default")
      (node (ref "U$33") (pin "B5") (pinfunction "P012_B5") (pintype "bidirectional"))
    )
    (net (code "71") (name "unconnected-(U$33-P023-PadC4)") (class "Default")
      (node (ref "U$33") (pin "C4") (pinfunction "P023_C4") (pintype "bidirectional"))
    )
    (net (code "72") (name "unconnected-(U$33-P024-PadC3)") (class "Default")
      (node (ref "U$33") (pin "C3") (pinfunction "P024_C3") (pintype "bidirectional"))
    )
    (net (code "73") (name "unconnected-(U$33-P025-PadC6)") (class "Default")
      (node (ref "U$33") (pin "C6") (pinfunction "P025_C6") (pintype "bidirectional"))
    )
    (net (code "74") (name "unconnected-(U$33-P026-PadD1)") (class "Default")
      (node (ref "U$33") (pin "D1") (pinfunction "P026_D1") (pintype "bidirectional"))
    )
    (net (code "75") (name "unconnected-(U$33-P027-PadD2)") (class "Default")
      (node (ref "U$33") (pin "D2") (pinfunction "P027_D2") (pintype "bidirectional"))
    )
    (net (code "76") (name "unconnected-(U$33-P028-PadD3)") (class "Default")
      (node (ref "U$33") (pin "D3") (pinfunction "P028_D3") (pintype "bidirectional"))
    )
    (net (code "77") (name "unconnected-(U$33-P30{slash}LED-Pad13)") (class "Default")
      (node (ref "U$33") (pin "13") (pinfunction "P30/LED_13") (pintype "bidirectional"))
    )
    (net (code "78") (name "unconnected-(U$33-P031-PadC1)") (class "Default")
      (node (ref "U$33") (pin "C1") (pinfunction "P031_C1") (pintype "bidirectional"))
    )
    (net (code "79") (name "unconnected-(U$33-P112-PadZ3)") (class "Default")
      (node (ref "U$33") (pin "Z3") (pinfunction "P112_Z3") (pintype "bidirectional"))
    )
    (net (code "80") (name "unconnected-(U$33-P114-PadZ5)") (class "Default")
      (node (ref "U$33") (pin "Z5") (pinfunction "P114_Z5") (pintype "bidirectional"))
    )
    (net (code "81") (name "unconnected-(U3-INT2-Pad9)") (class "Default")
      (node (ref "U3") (pin "9") (pinfunction "INT2_9") (pintype "bidirectional"))
    )
    (net (code "82") (name "unconnected-(U3-NC-Pad11)") (class "Default")
      (node (ref "U3") (pin "11") (pinfunction "NC_11") (pintype "bidirectional"))
    )
    (net (code "83") (name "unconnected-(U3-OCS-Pad10)") (class "Default")
      (node (ref "U3") (pin "10") (pinfunction "OCS_10") (pintype "bidirectional"))
    )
    (net (code "84") (name "unconnected-(U9-BP-Pad4)") (class "Default")
      (node (ref "U9") (pin "4") (pinfunction "BP_4") (pintype "input"))
    )
  )
)
